# fab.net
KiCad netlist of a schematic drawn in Altium Designer
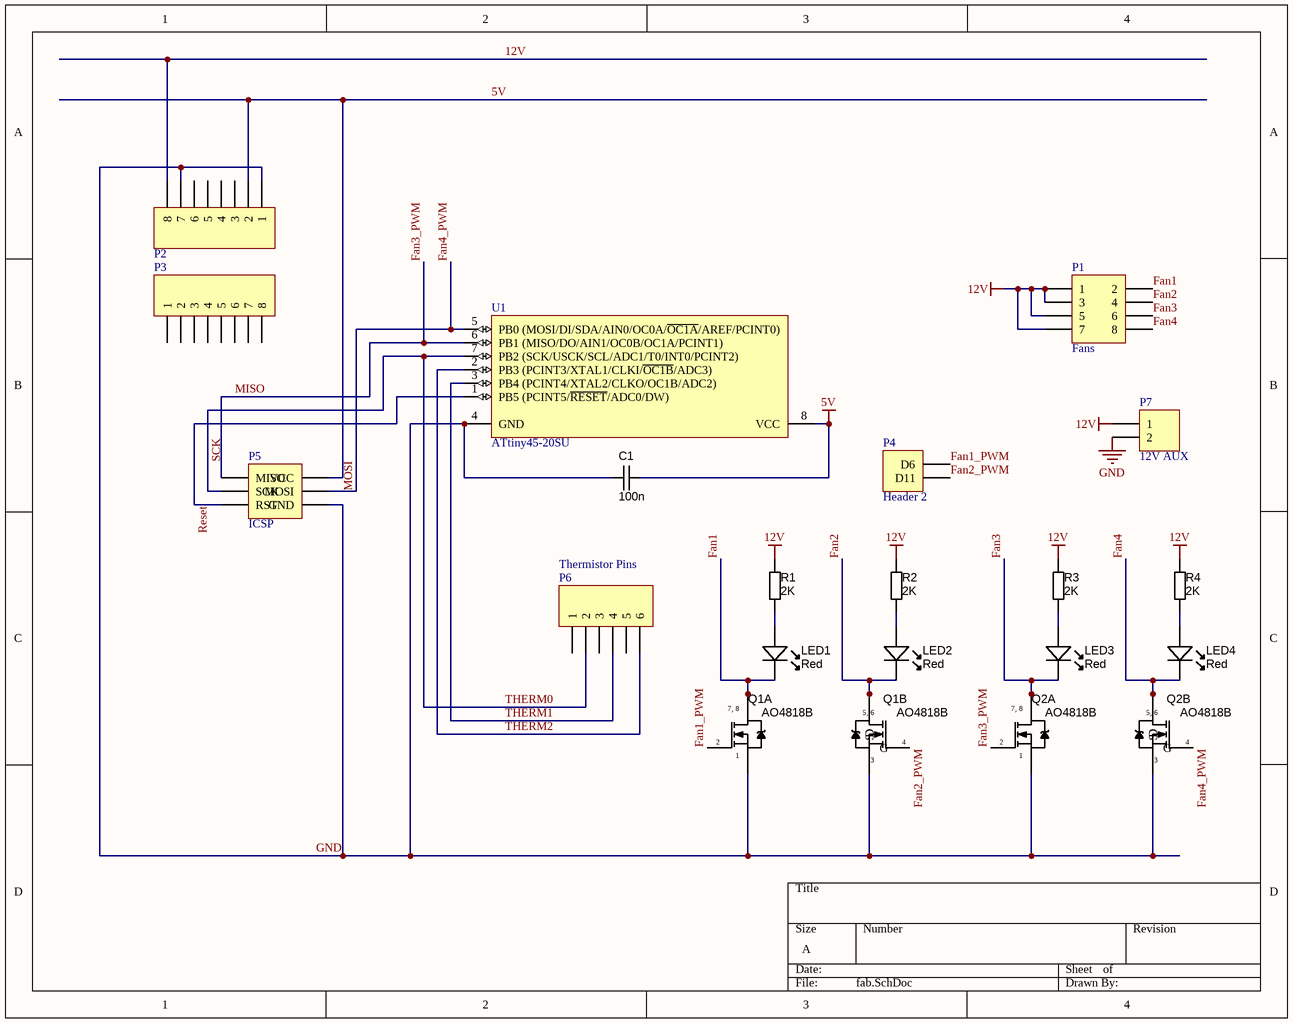
[diagram p0: fab.SchDoc]

(export (version "E")
  (design (tool "Eeschema 10.0.6"))
  (components
    (comp (ref "C1")
      (value "100n")
      (footprint "CAPC1005X55N")
      (description "Capacitor SMD Cer 100nF 10% 16V X5R 0402")
      (fields (field (name "TOLERANCE") "±10%"))
      (libsource (lib "PBL - Capacitors") (part "CAPC_100n_0402_X5R_16V_10%"))
    )
    (comp (ref "LED1")
      (value "Red")
      (footprint "LED-0603-RED")
      (description "LED 0603 SMD Hyper Red 630nm 220mcd 20mA")
      (libsource (lib "PBL - Light Sources") (part "LED_SMD_Red_0603_220mcd"))
    )
    (comp (ref "LED2")
      (value "Red")
      (footprint "LED-0603-RED")
      (description "LED 0603 SMD Hyper Red 630nm 220mcd 20mA")
      (libsource (lib "PBL - Light Sources") (part "LED_SMD_Red_0603_220mcd"))
    )
    (comp (ref "LED3")
      (value "Red")
      (footprint "LED-0603-RED")
      (description "LED 0603 SMD Hyper Red 630nm 220mcd 20mA")
      (libsource (lib "PBL - Light Sources") (part "LED_SMD_Red_0603_220mcd"))
    )
    (comp (ref "LED4")
      (value "Red")
      (footprint "LED-0603-RED")
      (description "LED 0603 SMD Hyper Red 630nm 220mcd 20mA")
      (libsource (lib "PBL - Light Sources") (part "LED_SMD_Red_0603_220mcd"))
    )
    (comp (ref "P1")
      (value "Fans")
      (footprint "HDR2X4")
      (description "Header, 4-Pin, Dual row")
      (fields (field (name "PUBLISHER") "Altium Limited"))
      (libsource (lib "Miscellaneous Connectors") (part "Header 4X2"))
    )
    (comp (ref "P2")
      (value "Header 8")
      (footprint "HDR1X8")
      (description "Header, 8-Pin")
      (fields (field (name "PUBLISHER") "Altium Limited"))
      (libsource (lib "Miscellaneous Connectors") (part "Header 8"))
    )
    (comp (ref "P3")
      (value "Header 8")
      (footprint "HDR1X8")
      (description "Header, 8-Pin")
      (fields (field (name "PUBLISHER") "Altium Limited"))
      (libsource (lib "") (part "Header 8_1"))
    )
    (comp (ref "P4")
      (value "Header 2")
      (footprint "HDR1X2")
      (description "Header, 2-Pin")
      (fields (field (name "PUBLISHER") "Altium Limited"))
      (libsource (lib "Miscellaneous Connectors") (part "Header 2"))
    )
    (comp (ref "P5")
      (value "ICSP")
      (footprint "ICSP Pads")
      (description "Header, 3-Pin, Dual row")
      (fields (field (name "PUBLISHER") "Altium Limited"))
      (libsource (lib "Miscellaneous Connectors") (part "Header 3X2"))
    )
    (comp (ref "P6")
      (value "Thermistor Pins")
      (footprint "HDR1X6")
      (description "Header, 6-Pin")
      (fields (field (name "PUBLISHER") "Altium Limited"))
      (libsource (lib "Miscellaneous Connectors") (part "Header 6"))
    )
    (comp (ref "P7")
      (value "12V AUX")
      (footprint "HDR1X2")
      (description "Header, 2-Pin")
      (fields (field (name "PUBLISHER") "Altium Limited"))
      (libsource (lib "") (part "Header 2_1"))
    )
    (comp (ref "Q1")
      (value "MOSFET_AO4818B")
      (footprint "SOIC127P600X175-8AN")
      (description "MOSFET Dual-Channel 30V 8.5A SOIC-8 SMD")
      (fields (field (name "MANUFACTURER PART NUMBER 1") "AO4818B"))
      (libsource (lib "") (part "MOSFET_AO4818B_1"))
    )
    (comp (ref "Q2")
      (value "MOSFET_AO4818B")
      (footprint "SOIC127P600X175-8AN")
      (description "MOSFET Dual-Channel 30V 8.5A SOIC-8 SMD")
      (fields (field (name "MANUFACTURER PART NUMBER 1") "AO4818B"))
      (libsource (lib "") (part "MOSFET_AO4818B_1"))
    )
    (comp (ref "R1")
      (value "2K")
      (footprint "RESC1608X55N")
      (description "Resistor SMD chip 330 Ohm 0.1W 5% 0603")
      (fields (field (name "TOLERANCE") "±5%") (field (name "Comment") "Thick Film"))
      (libsource (lib "PBL - Resistors") (part "RES_330R_0603_5%"))
    )
    (comp (ref "R2")
      (value "2K")
      (footprint "RESC1608X55N")
      (description "Resistor SMD chip 330 Ohm 0.1W 5% 0603")
      (fields (field (name "TOLERANCE") "±5%") (field (name "Comment") "Thick Film"))
      (libsource (lib "PBL - Resistors") (part "RES_330R_0603_5%"))
    )
    (comp (ref "R3")
      (value "2K")
      (footprint "RESC1608X55N")
      (description "Resistor SMD chip 330 Ohm 0.1W 5% 0603")
      (fields (field (name "TOLERANCE") "±5%") (field (name "Comment") "Thick Film"))
      (libsource (lib "PBL - Resistors") (part "RES_330R_0603_5%"))
    )
    (comp (ref "R4")
      (value "2K")
      (footprint "RESC1608X55N")
      (description "Resistor SMD chip 330 Ohm 0.1W 5% 0603")
      (fields (field (name "TOLERANCE") "±5%") (field (name "Comment") "Thick Film"))
      (libsource (lib "PBL - Resistors") (part "RES_330R_0603_5%"))
    )
    (comp (ref "U1")
      (value "ATtiny45-20SU")
      (footprint "8S2_N")
      (libsource (lib "Atmel Microcontroller tinyAVR") (part "ATtiny45-20SU"))
    )
  )
  (nets
    (net (code "1") (name "/Fan1") (class "Default")
      (node (ref "LED1") (pin "K") (pinfunction "K_K") (pintype "passive"))
      (node (ref "P1") (pin "2") (pinfunction "2_2") (pintype "passive"))
      (node (ref "Q1") (pin "7") (pinfunction "D_7") (pintype "passive"))
      (node (ref "Q1") (pin "8") (pinfunction "D_8") (pintype "passive"))
    )
    (net (code "2") (name "/Fan1_PWM") (class "Default")
      (node (ref "P4") (pin "2") (pinfunction "D6_2") (pintype "passive"))
      (node (ref "Q1") (pin "2") (pinfunction "G_2") (pintype "passive"))
    )
    (net (code "3") (name "/Fan2") (class "Default")
      (node (ref "LED2") (pin "K") (pinfunction "K_K") (pintype "passive"))
      (node (ref "P1") (pin "4") (pinfunction "4_4") (pintype "passive"))
      (node (ref "Q1") (pin "5") (pinfunction "D_5") (pintype "passive"))
      (node (ref "Q1") (pin "6") (pinfunction "D_6") (pintype "passive"))
    )
    (net (code "4") (name "/Fan2_PWM") (class "Default")
      (node (ref "P4") (pin "1") (pinfunction "D11_1") (pintype "passive"))
      (node (ref "Q1") (pin "4") (pinfunction "G_4") (pintype "passive"))
    )
    (net (code "5") (name "/Fan3") (class "Default")
      (node (ref "LED3") (pin "K") (pinfunction "K_K") (pintype "passive"))
      (node (ref "P1") (pin "6") (pinfunction "6_6") (pintype "passive"))
      (node (ref "Q2") (pin "7") (pinfunction "D_7") (pintype "passive"))
      (node (ref "Q2") (pin "8") (pinfunction "D_8") (pintype "passive"))
    )
    (net (code "6") (name "/Fan3_PWM") (class "Default")
      (node (ref "P5") (pin "0") (pinfunction "MISO_0") (pintype "passive"))
      (node (ref "Q2") (pin "2") (pinfunction "G_2") (pintype "passive"))
      (node (ref "U1") (pin "6") (pinfunction "PB1_(MISO/DO/AIN1/OC0B/OC1A/PCINT1)_6") (pintype "bidirectional"))
    )
    (net (code "7") (name "/Fan4") (class "Default")
      (node (ref "LED4") (pin "K") (pinfunction "K_K") (pintype "passive"))
      (node (ref "P1") (pin "8") (pinfunction "8_8") (pintype "passive"))
      (node (ref "Q2") (pin "5") (pinfunction "D_5") (pintype "passive"))
      (node (ref "Q2") (pin "6") (pinfunction "D_6") (pintype "passive"))
    )
    (net (code "8") (name "/Fan4_PWM") (class "Default")
      (node (ref "P5") (pin "3") (pinfunction "MOSI_3") (pintype "passive"))
      (node (ref "Q2") (pin "4") (pinfunction "G_4") (pintype "passive"))
      (node (ref "U1") (pin "5") (pinfunction "PB0_(MOSI/DI/SDA/AIN0/OC0A/~{OC1A}/AREF/PCINT0)_5") (pintype "bidirectional"))
    )
    (net (code "9") (name "/Reset") (class "Default")
      (node (ref "P5") (pin "4") (pinfunction "RST_4") (pintype "passive"))
      (node (ref "U1") (pin "1") (pinfunction "PB5_(PCINT5/~{RESET}/ADC0/DW)_1") (pintype "bidirectional"))
    )
    (net (code "10") (name "/SCK") (class "Default")
      (node (ref "P5") (pin "2") (pinfunction "SCK_2") (pintype "passive"))
      (node (ref "P6") (pin "2") (pinfunction "2_2") (pintype "passive"))
      (node (ref "U1") (pin "7") (pinfunction "PB2_(SCK/USCK/SCL/ADC1/T0/INT0/PCINT2)_7") (pintype "bidirectional"))
    )
    (net (code "11") (name "/THERM1") (class "Default")
      (node (ref "P6") (pin "4") (pinfunction "4_4") (pintype "passive"))
      (node (ref "U1") (pin "3") (pinfunction "PB4_(PCINT4/XTAL2/CLKO/OC1B/ADC2)_3") (pintype "bidirectional"))
    )
    (net (code "12") (name "/THERM2") (class "Default")
      (node (ref "P6") (pin "6") (pinfunction "6_6") (pintype "passive"))
      (node (ref "U1") (pin "2") (pinfunction "PB3_(PCINT3/XTAL1/CLKI/~{OC1B}/ADC3)_2") (pintype "bidirectional"))
    )
    (net (code "13") (name "5V") (class "Default")
      (node (ref "C1") (pin "2") (pintype "passive"))
      (node (ref "P2") (pin "2") (pinfunction "2_2") (pintype "passive"))
      (node (ref "P5") (pin "1") (pinfunction "VCC_1") (pintype "passive"))
      (node (ref "U1") (pin "8") (pinfunction "VCC_8") (pintype "power_in"))
    )
    (net (code "14") (name "12V") (class "Default")
      (node (ref "P1") (pin "1") (pinfunction "1_1") (pintype "passive"))
      (node (ref "P1") (pin "3") (pinfunction "3_3") (pintype "passive"))
      (node (ref "P1") (pin "5") (pinfunction "5_5") (pintype "passive"))
      (node (ref "P1") (pin "7") (pinfunction "7_7") (pintype "passive"))
      (node (ref "P2") (pin "8") (pinfunction "8_8") (pintype "passive"))
      (node (ref "P7") (pin "1") (pinfunction "1_1") (pintype "passive"))
      (node (ref "R1") (pin "1") (pinfunction "1_1") (pintype "passive"))
      (node (ref "R2") (pin "1") (pinfunction "1_1") (pintype "passive"))
      (node (ref "R3") (pin "1") (pinfunction "1_1") (pintype "passive"))
      (node (ref "R4") (pin "1") (pinfunction "1_1") (pintype "passive"))
    )
    (net (code "15") (name "GND") (class "Default")
      (node (ref "C1") (pin "1") (pintype "passive"))
      (node (ref "P2") (pin "1") (pinfunction "1_1") (pintype "passive"))
      (node (ref "P2") (pin "7") (pinfunction "7_7") (pintype "passive"))
      (node (ref "P5") (pin "5") (pinfunction "GND_5") (pintype "passive"))
      (node (ref "P7") (pin "2") (pinfunction "2_2") (pintype "passive"))
      (node (ref "Q1") (pin "1") (pinfunction "S_1") (pintype "passive"))
      (node (ref "Q1") (pin "3") (pinfunction "S_3") (pintype "passive"))
      (node (ref "Q2") (pin "1") (pinfunction "S_1") (pintype "passive"))
      (node (ref "Q2") (pin "3") (pinfunction "S_3") (pintype "passive"))
      (node (ref "U1") (pin "4") (pinfunction "GND_4") (pintype "power_in"))
    )
    (net (code "16") (name "Net-(LED1-PadA)") (class "Default")
      (node (ref "LED1") (pin "A") (pinfunction "A_A") (pintype "passive"))
      (node (ref "R1") (pin "2") (pinfunction "2_2") (pintype "passive"))
    )
    (net (code "17") (name "Net-(LED2-PadA)") (class "Default")
      (node (ref "LED2") (pin "A") (pinfunction "A_A") (pintype "passive"))
      (node (ref "R2") (pin "2") (pinfunction "2_2") (pintype "passive"))
    )
    (net (code "18") (name "Net-(LED3-PadA)") (class "Default")
      (node (ref "LED3") (pin "A") (pinfunction "A_A") (pintype "passive"))
      (node (ref "R3") (pin "2") (pinfunction "2_2") (pintype "passive"))
    )
    (net (code "19") (name "Net-(LED4-PadA)") (class "Default")
      (node (ref "LED4") (pin "A") (pinfunction "A_A") (pintype "passive"))
      (node (ref "R4") (pin "2") (pinfunction "2_2") (pintype "passive"))
    )
    (net (code "20") (name "unconnected-(P2-Pad3)") (class "Default")
      (node (ref "P2") (pin "3") (pinfunction "3_3") (pintype "passive"))
    )
    (net (code "21") (name "unconnected-(P2-Pad4)") (class "Default")
      (node (ref "P2") (pin "4") (pinfunction "4_4") (pintype "passive"))
    )
    (net (code "22") (name "unconnected-(P2-Pad5)") (class "Default")
      (node (ref "P2") (pin "5") (pinfunction "5_5") (pintype "passive"))
    )
    (net (code "23") (name "unconnected-(P2-Pad6)") (class "Default")
      (node (ref "P2") (pin "6") (pinfunction "6_6") (pintype "passive"))
    )
    (net (code "24") (name "unconnected-(P3-Pad1)") (class "Default")
      (node (ref "P3") (pin "1") (pinfunction "1_1") (pintype "passive"))
    )
    (net (code "25") (name "unconnected-(P3-Pad2)") (class "Default")
      (node (ref "P3") (pin "2") (pinfunction "2_2") (pintype "passive"))
    )
    (net (code "26") (name "unconnected-(P3-Pad3)") (class "Default")
      (node (ref "P3") (pin "3") (pinfunction "3_3") (pintype "passive"))
    )
    (net (code "27") (name "unconnected-(P3-Pad4)") (class "Default")
      (node (ref "P3") (pin "4") (pinfunction "4_4") (pintype "passive"))
    )
    (net (code "28") (name "unconnected-(P3-Pad5)") (class "Default")
      (node (ref "P3") (pin "5") (pinfunction "5_5") (pintype "passive"))
    )
    (net (code "29") (name "unconnected-(P3-Pad6)") (class "Default")
      (node (ref "P3") (pin "6") (pinfunction "6_6") (pintype "passive"))
    )
    (net (code "30") (name "unconnected-(P3-Pad7)") (class "Default")
      (node (ref "P3") (pin "7") (pinfunction "7_7") (pintype "passive"))
    )
    (net (code "31") (name "unconnected-(P3-Pad8)") (class "Default")
      (node (ref "P3") (pin "8") (pinfunction "8_8") (pintype "passive"))
    )
    (net (code "32") (name "unconnected-(P6-Pad1)") (class "Default")
      (node (ref "P6") (pin "1") (pinfunction "1_1") (pintype "passive"))
    )
    (net (code "33") (name "unconnected-(P6-Pad3)") (class "Default")
      (node (ref "P6") (pin "3") (pinfunction "3_3") (pintype "passive"))
    )
    (net (code "34") (name "unconnected-(P6-Pad5)") (class "Default")
      (node (ref "P6") (pin "5") (pinfunction "5_5") (pintype "passive"))
    )
  )
)
